# OpenPack_BATMOD_V2p0_PWR.net
KiCad netlist of a schematic drawn in Altium Designer
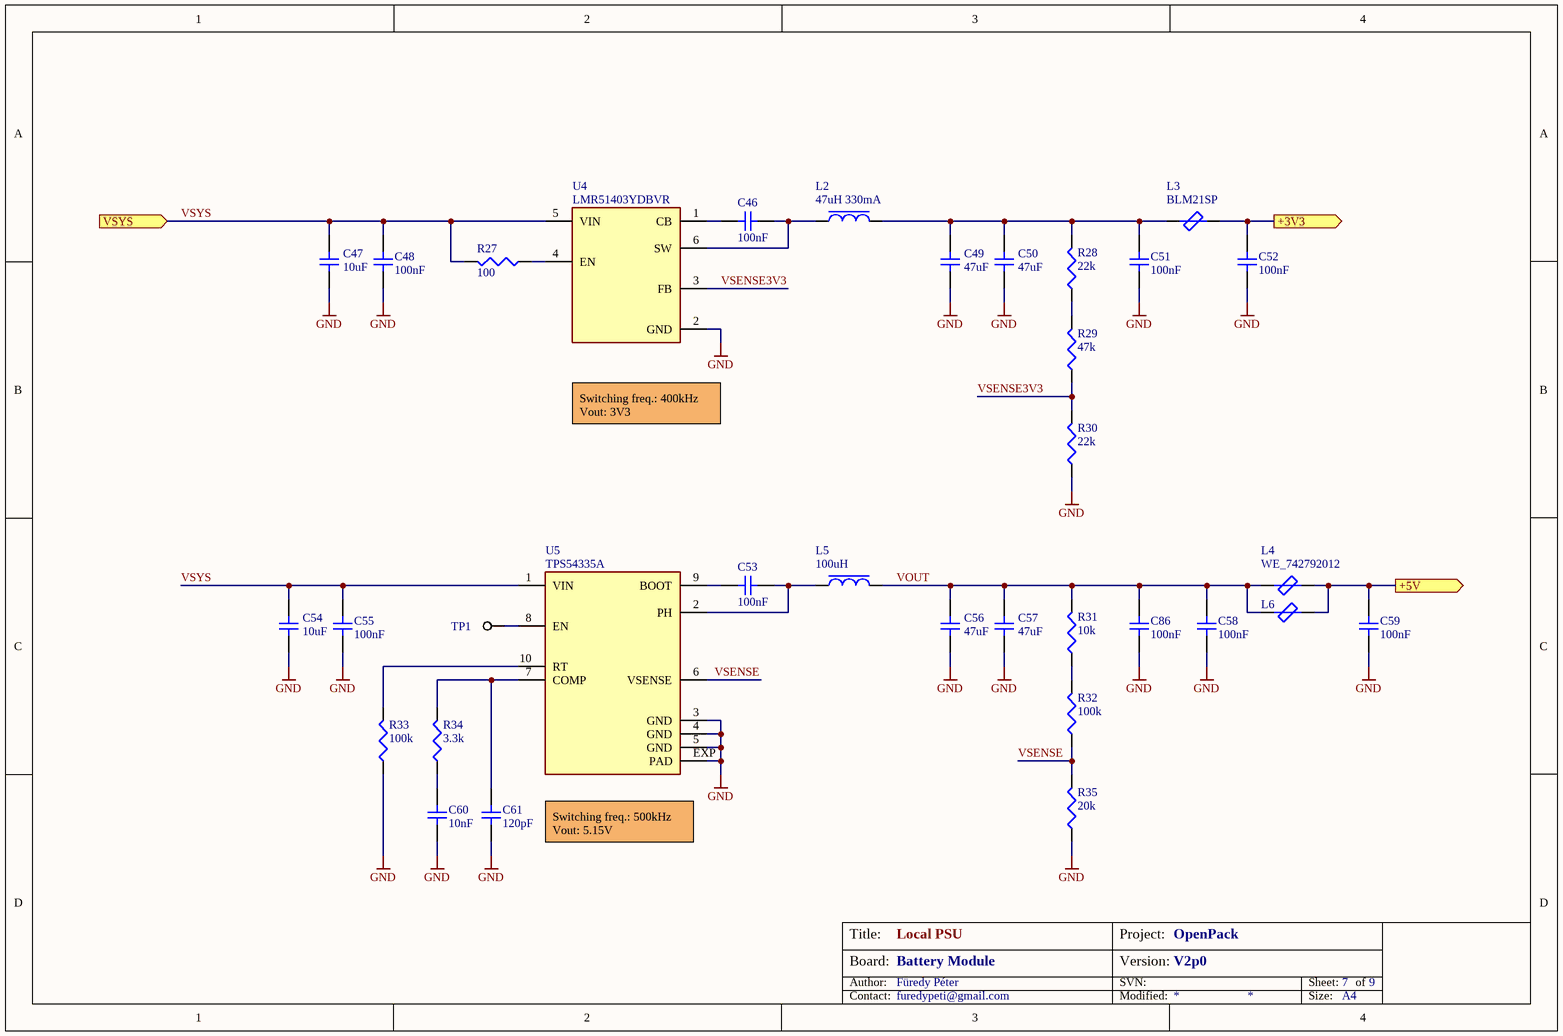
[diagram p0: OpenPack_BATMOD_V2p0_PWR.SchDoc]

(export (version "E")
  (design (tool "Eeschema 10.0.6"))
  (components
    (comp (ref "C46")
      (value "100nF")
      (footprint "CAP_0603")
      (description "MLCC capacitor")
      (libsource (lib "SCHLIB") (part "NP-CAPACITOR"))
    )
    (comp (ref "C47")
      (value "10uF")
      (footprint "CAP_1210")
      (description "UMK325BJ106KM-P")
      (fields (field (name "PART NUMBER") "810-CGA6P1X7R1N106K2"))
      (libsource (lib "SCHLIB") (part "NP-CAPACITOR"))
    )
    (comp (ref "C48")
      (value "100nF")
      (footprint "CAP_0603")
      (description "MLCC capacitor")
      (libsource (lib "SCHLIB") (part "NP-CAPACITOR"))
    )
    (comp (ref "C49")
      (value "47uF")
      (footprint "CAP_1210")
      (description "Np-Cap")
      (fields (field (name "PART NUMBER") "80-C1210C476M4P"))
      (libsource (lib "SCHLIB") (part "NP-CAPACITOR"))
    )
    (comp (ref "C50")
      (value "47uF")
      (footprint "CAP_1210")
      (description "Np-Cap")
      (fields (field (name "PART NUMBER") "80-C1210C476M4P"))
      (libsource (lib "SCHLIB") (part "NP-CAPACITOR"))
    )
    (comp (ref "C51")
      (value "100nF")
      (footprint "CAP_0603")
      (description "MLCC capacitor")
      (libsource (lib "SCHLIB") (part "NP-CAPACITOR"))
    )
    (comp (ref "C52")
      (value "100nF")
      (footprint "CAP_0603")
      (description "MLCC capacitor")
      (libsource (lib "SCHLIB") (part "NP-CAPACITOR"))
    )
    (comp (ref "C53")
      (value "100nF")
      (footprint "CAP_0603")
      (description "MLCC capacitor")
      (libsource (lib "SCHLIB") (part "NP-CAPACITOR"))
    )
    (comp (ref "C54")
      (value "10uF")
      (footprint "CAP_1210")
      (description "UMK325BJ106KM-P")
      (fields (field (name "PART NUMBER") "810-CGA6P1X7R1N106K2"))
      (libsource (lib "SCHLIB") (part "NP-CAPACITOR"))
    )
    (comp (ref "C55")
      (value "100nF")
      (footprint "CAP_0603")
      (description "MLCC capacitor")
      (libsource (lib "SCHLIB") (part "NP-CAPACITOR"))
    )
    (comp (ref "C56")
      (value "47uF")
      (footprint "CAP_1210")
      (description "Np-Cap")
      (fields (field (name "PART NUMBER") "80-C1210C476M4P"))
      (libsource (lib "SCHLIB") (part "NP-CAPACITOR"))
    )
    (comp (ref "C57")
      (value "47uF")
      (footprint "CAP_1210")
      (description "Np-Cap")
      (fields (field (name "PART NUMBER") "80-C1210C476M4P"))
      (libsource (lib "SCHLIB") (part "NP-CAPACITOR"))
    )
    (comp (ref "C58")
      (value "100nF")
      (footprint "CAP_0603")
      (description "MLCC capacitor")
      (libsource (lib "SCHLIB") (part "NP-CAPACITOR"))
    )
    (comp (ref "C59")
      (value "100nF")
      (footprint "CAP_0603")
      (description "MLCC capacitor")
      (libsource (lib "SCHLIB") (part "NP-CAPACITOR"))
    )
    (comp (ref "C60")
      (value "10nF")
      (footprint "CAP_0603")
      (description "MLCC capacitor")
      (libsource (lib "SCHLIB") (part "NP-CAPACITOR"))
    )
    (comp (ref "C61")
      (value "120pF")
      (footprint "CAP_0603")
      (description "MLCC capacitor")
      (libsource (lib "SCHLIB") (part "NP-CAPACITOR"))
    )
    (comp (ref "C86")
      (value "100nF")
      (footprint "CAP_0603")
      (description "MLCC capacitor")
      (libsource (lib "SCHLIB") (part "NP-CAPACITOR"))
    )
    (comp (ref "L2")
      (value "47uH 330mA")
      (footprint "IND_1210")
      (description "Power inductor")
      (fields (field (name "PART NUMBER") "81-LQH32PN470MN0L"))
      (libsource (lib "SCHLIB") (part "Inductance - 47uH"))
    )
    (comp (ref "L3")
      (value "BLM21SP")
      (footprint "IND-0805")
      (description "Chip Ferrite Bead, 1000R @100MHz, 1.6A")
      (fields (field (name "PART NUMBER") "81-BLM21SP102SN1D"))
      (libsource (lib "SCHLIB") (part "BLM21SP102SN1D"))
    )
    (comp (ref "L4")
      (value "WE_742792012")
      (footprint "IND-0805")
      (description "Chip Ferrite Bead, 33R @100MHz, 4A")
      (fields (field (name "PART NUMBER") "710-742792012"))
      (libsource (lib "SCHLIB") (part "WE_742792012"))
    )
    (comp (ref "L5")
      (value "100uH")
      (footprint "IND_2")
      (description "Ferrit core coil, 22uH 2.85A, 75mR")
      (fields (field (name "PART NUMBER") "994-MSS1038T-223MLC"))
      (libsource (lib "SCHLIB") (part "Inductance - 22uH"))
    )
    (comp (ref "L6")
      (value "WE_742792012")
      (footprint "IND-0805")
      (description "Chip Ferrite Bead, 33R @100MHz, 4A")
      (fields (field (name "PART NUMBER") "710-742792012"))
      (libsource (lib "SCHLIB") (part "WE_742792012"))
    )
    (comp (ref "R27")
      (value "100")
      (footprint "RES-0603")
      (description "Metal Film Resistor")
      (libsource (lib "SCHLIB") (part "RESISTOR"))
    )
    (comp (ref "R28")
      (value "22k")
      (footprint "RES-0603")
      (description "Metal Film Resistor")
      (libsource (lib "SCHLIB") (part "RESISTOR"))
    )
    (comp (ref "R29")
      (value "47k")
      (footprint "RES-0603")
      (description "Metal Film Resistor")
      (libsource (lib "SCHLIB") (part "RESISTOR"))
    )
    (comp (ref "R30")
      (value "22k")
      (footprint "RES-0603")
      (description "Metal Film Resistor")
      (libsource (lib "SCHLIB") (part "RESISTOR"))
    )
    (comp (ref "R31")
      (value "10k")
      (footprint "RES-0603")
      (description "Metal Film Resistor")
      (libsource (lib "SCHLIB") (part "RESISTOR"))
    )
    (comp (ref "R32")
      (value "100k")
      (footprint "RES-0603")
      (description "Metal Film Resistor")
      (libsource (lib "SCHLIB") (part "RESISTOR"))
    )
    (comp (ref "R33")
      (value "100k")
      (footprint "RES-0603")
      (description "Metal Film Resistor")
      (libsource (lib "SCHLIB") (part "RESISTOR"))
    )
    (comp (ref "R34")
      (value "3.3k")
      (footprint "RES-0603")
      (description "Metal Film Resistor")
      (libsource (lib "SCHLIB") (part "RESISTOR"))
    )
    (comp (ref "R35")
      (value "20k")
      (footprint "RES-0603")
      (description "Metal Film Resistor")
      (libsource (lib "SCHLIB") (part "RESISTOR"))
    )
    (comp (ref "TP1")
      (value "TESTPOINT")
      (footprint "TESTPOINT1MM")
      (description "SMD testpoint")
      (libsource (lib "SCHLIB") (part "TESTPOINT"))
    )
    (comp (ref "U4")
      (value "LMR51403YDBVR")
      (footprint "SOT-23-6")
      (description "Switching Voltage Regulators 4.5V-to-42V 0.3A syn chronous buck conve")
      (fields (field (name "PART NUMBER") "595-LMR51403YDBVR"))
      (libsource (lib "SCHLIB") (part "LMR51403YDBVR"))
    )
    (comp (ref "U5")
      (value "TPS54335A")
      (footprint "VSON-10")
      (description "Switching Voltage Regulators 4.5Vto28VInp 3A Sync Step-Down Converter A 595-TPS54335ADRCT")
      (fields (field (name "PART NUMBER") "595-TPS54335ADRCR"))
      (libsource (lib "SCHLIB") (part "TPS54335A"))
    )
  )
  (nets
    (net (code "1") (name "/+3V3") (class "Default")
      (node (ref "C52") (pin "1") (pinfunction "1_1") (pintype "passive"))
      (node (ref "L3") (pin "2") (pinfunction "2_2") (pintype "passive"))
    )
    (net (code "2") (name "/+5V") (class "Default")
      (node (ref "C59") (pin "1") (pinfunction "1_1") (pintype "passive"))
      (node (ref "L4") (pin "2") (pinfunction "2_2") (pintype "passive"))
      (node (ref "L6") (pin "2") (pinfunction "2_2") (pintype "passive"))
    )
    (net (code "3") (name "/VOUT") (class "Default")
      (node (ref "C56") (pin "2") (pinfunction "2_2") (pintype "passive"))
      (node (ref "C57") (pin "2") (pinfunction "2_2") (pintype "passive"))
      (node (ref "C58") (pin "1") (pinfunction "1_1") (pintype "passive"))
      (node (ref "C86") (pin "1") (pinfunction "1_1") (pintype "passive"))
      (node (ref "L4") (pin "1") (pinfunction "1_1") (pintype "passive"))
      (node (ref "L5") (pin "2") (pinfunction "2_2") (pintype "passive"))
      (node (ref "L6") (pin "1") (pinfunction "1_1") (pintype "passive"))
      (node (ref "R31") (pin "2") (pintype "passive"))
    )
    (net (code "4") (name "/VSENSE") (class "Default")
      (node (ref "R32") (pin "1") (pintype "passive"))
      (node (ref "R35") (pin "2") (pintype "passive"))
      (node (ref "U5") (pin "6") (pinfunction "VSENSE_6") (pintype "passive"))
    )
    (net (code "5") (name "/VSENSE3V3") (class "Default")
      (node (ref "R29") (pin "1") (pintype "passive"))
      (node (ref "R30") (pin "2") (pintype "passive"))
      (node (ref "U4") (pin "3") (pinfunction "FB_3") (pintype "passive"))
    )
    (net (code "6") (name "/VSYS") (class "Default")
      (node (ref "C47") (pin "2") (pinfunction "2_2") (pintype "passive"))
      (node (ref "C48") (pin "1") (pinfunction "1_1") (pintype "passive"))
      (node (ref "C54") (pin "2") (pinfunction "2_2") (pintype "passive"))
      (node (ref "C55") (pin "1") (pinfunction "1_1") (pintype "passive"))
      (node (ref "R27") (pin "2") (pintype "passive"))
      (node (ref "U4") (pin "5") (pinfunction "VIN_5") (pintype "passive"))
      (node (ref "U5") (pin "1") (pinfunction "VIN_1") (pintype "passive"))
    )
    (net (code "7") (name "GND") (class "Default")
      (node (ref "C47") (pin "1") (pinfunction "1_1") (pintype "passive"))
      (node (ref "C48") (pin "2") (pinfunction "2_2") (pintype "passive"))
      (node (ref "C49") (pin "1") (pinfunction "1_1") (pintype "passive"))
      (node (ref "C50") (pin "1") (pinfunction "1_1") (pintype "passive"))
      (node (ref "C51") (pin "2") (pinfunction "2_2") (pintype "passive"))
      (node (ref "C52") (pin "2") (pinfunction "2_2") (pintype "passive"))
      (node (ref "C54") (pin "1") (pinfunction "1_1") (pintype "passive"))
      (node (ref "C55") (pin "2") (pinfunction "2_2") (pintype "passive"))
      (node (ref "C56") (pin "1") (pinfunction "1_1") (pintype "passive"))
      (node (ref "C57") (pin "1") (pinfunction "1_1") (pintype "passive"))
      (node (ref "C58") (pin "2") (pinfunction "2_2") (pintype "passive"))
      (node (ref "C59") (pin "2") (pinfunction "2_2") (pintype "passive"))
      (node (ref "C60") (pin "2") (pinfunction "2_2") (pintype "passive"))
      (node (ref "C61") (pin "2") (pinfunction "2_2") (pintype "passive"))
      (node (ref "C86") (pin "2") (pinfunction "2_2") (pintype "passive"))
      (node (ref "R30") (pin "1") (pintype "passive"))
      (node (ref "R33") (pin "1") (pintype "passive"))
      (node (ref "R35") (pin "1") (pintype "passive"))
      (node (ref "U4") (pin "2") (pinfunction "GND_2") (pintype "passive"))
      (node (ref "U5") (pin "3") (pinfunction "GND_3") (pintype "passive"))
      (node (ref "U5") (pin "4") (pinfunction "GND_4") (pintype "passive"))
      (node (ref "U5") (pin "5") (pinfunction "GND_5") (pintype "passive"))
      (node (ref "U5") (pin "EXP") (pinfunction "PAD_EXP") (pintype "passive"))
    )
    (net (code "8") (name "Net-(C49-Pad2)") (class "Default")
      (node (ref "C49") (pin "2") (pinfunction "2_2") (pintype "passive"))
      (node (ref "C50") (pin "2") (pinfunction "2_2") (pintype "passive"))
      (node (ref "C51") (pin "1") (pinfunction "1_1") (pintype "passive"))
      (node (ref "L2") (pin "2") (pinfunction "2_2") (pintype "passive"))
      (node (ref "L3") (pin "1") (pinfunction "1_1") (pintype "passive"))
      (node (ref "R28") (pin "2") (pintype "passive"))
    )
    (net (code "9") (name "Net-(C60-Pad1)") (class "Default")
      (node (ref "C60") (pin "1") (pinfunction "1_1") (pintype "passive"))
      (node (ref "R34") (pin "1") (pintype "passive"))
    )
    (net (code "10") (name "Net-(R28-Pad1)") (class "Default")
      (node (ref "R28") (pin "1") (pintype "passive"))
      (node (ref "R29") (pin "2") (pintype "passive"))
    )
    (net (code "11") (name "Net-(R31-Pad1)") (class "Default")
      (node (ref "R31") (pin "1") (pintype "passive"))
      (node (ref "R32") (pin "2") (pintype "passive"))
    )
    (net (code "12") (name "Net-(U4-CB)") (class "Default")
      (node (ref "C46") (pin "2") (pinfunction "2_2") (pintype "passive"))
      (node (ref "U4") (pin "1") (pinfunction "CB_1") (pintype "passive"))
    )
    (net (code "13") (name "Net-(U4-EN)") (class "Default")
      (node (ref "R27") (pin "1") (pintype "passive"))
      (node (ref "U4") (pin "4") (pinfunction "EN_4") (pintype "passive"))
    )
    (net (code "14") (name "Net-(U4-SW)") (class "Default")
      (node (ref "C46") (pin "1") (pinfunction "1_1") (pintype "passive"))
      (node (ref "L2") (pin "1") (pinfunction "1_1") (pintype "passive"))
      (node (ref "U4") (pin "6") (pinfunction "SW_6") (pintype "passive"))
    )
    (net (code "15") (name "Net-(U5-BOOT)") (class "Default")
      (node (ref "C53") (pin "2") (pinfunction "2_2") (pintype "passive"))
      (node (ref "U5") (pin "9") (pinfunction "BOOT_9") (pintype "passive"))
    )
    (net (code "16") (name "Net-(U5-COMP)") (class "Default")
      (node (ref "C61") (pin "1") (pinfunction "1_1") (pintype "passive"))
      (node (ref "R34") (pin "2") (pintype "passive"))
      (node (ref "U5") (pin "7") (pinfunction "COMP_7") (pintype "passive"))
    )
    (net (code "17") (name "Net-(U5-EN)") (class "Default")
      (node (ref "TP1") (pin "0") (pintype "passive"))
      (node (ref "U5") (pin "8") (pinfunction "EN_8") (pintype "passive"))
    )
    (net (code "18") (name "Net-(U5-PH)") (class "Default")
      (node (ref "C53") (pin "1") (pinfunction "1_1") (pintype "passive"))
      (node (ref "L5") (pin "1") (pinfunction "1_1") (pintype "passive"))
      (node (ref "U5") (pin "2") (pinfunction "PH_2") (pintype "passive"))
    )
    (net (code "19") (name "Net-(U5-RT)") (class "Default")
      (node (ref "R33") (pin "2") (pintype "passive"))
      (node (ref "U5") (pin "10") (pinfunction "RT_10") (pintype "passive"))
    )
  )
)
